# 5V_Power_Supply.net
KiCad netlist of a schematic drawn in Altium Designer
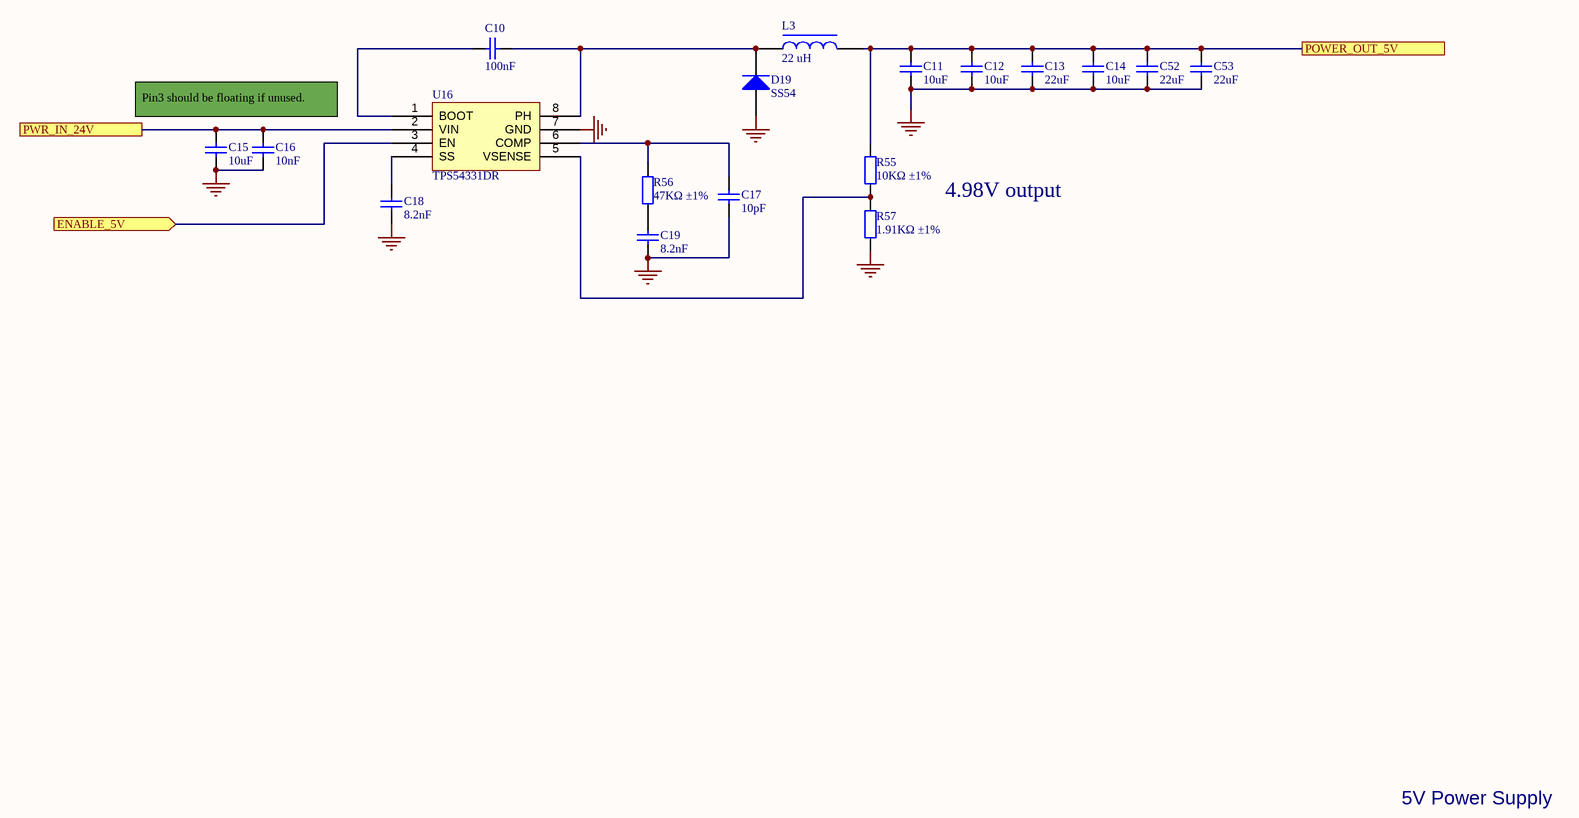
[diagram p0: 5V_Power_Supply.SchDoc]

(export (version "E")
  (design (tool "Eeschema 10.0.6"))
  (components
    (comp (ref "C10")
      (value "100nF")
      (footprint "0603_C")
      (description "50V 100nF X7R ±10% 0603 Multilayer Ceramic Capacitors MLCC - SMD/SMT ROHS")
      (fields
        (field (name "MANUFACTURER") "YAGEO")
        (field (name "MANUFACTURER PART NUMBER") "CC0603KRX7R9BB104")
      )
      (libsource (lib "Sienci_Labs") (part "0603 100nF (104) 10% 50V"))
    )
    (comp (ref "C11")
      (value "10uF")
      (footprint "1206_C")
      (description "50V 10uF X5R ±10% 1206 Multilayer Ceramic Capacitors MLCC - SMD/SMT ROHS")
      (fields
        (field (name "MANUFACTURER") "Samsung Electro-Mechanics")
        (field (name "MANUFACTURER PART NUMBER") "CL31A106KBHNNNE")
      )
      (libsource (lib "Sienci_Labs") (part "1206 10uF (106) 10% 50V"))
    )
    (comp (ref "C12")
      (value "10uF")
      (footprint "1206_C")
      (description "50V 10uF X5R ±10% 1206 Multilayer Ceramic Capacitors MLCC - SMD/SMT ROHS")
      (fields
        (field (name "MANUFACTURER") "Samsung Electro-Mechanics")
        (field (name "MANUFACTURER PART NUMBER") "CL31A106KBHNNNE")
      )
      (libsource (lib "Sienci_Labs") (part "1206 10uF (106) 10% 50V"))
    )
    (comp (ref "C13")
      (value "22uF")
      (footprint "0805_C")
      (description "25V 22uF X5R ±20% 0805 Multilayer Ceramic Capacitors MLCC - SMD/SMT ROHS")
      (fields (field (name "MANUFACTURER") "Samsung Electro-Mechanics") (field (name "TOLERANCE") "20%"))
      (libsource (lib "Sienci_Labs") (part "0805 22uF (226) 20% 25V"))
    )
    (comp (ref "C14")
      (value "10uF")
      (footprint "1206_C")
      (description "50V 10uF X5R ±10% 1206 Multilayer Ceramic Capacitors MLCC - SMD/SMT ROHS")
      (fields
        (field (name "MANUFACTURER") "Samsung Electro-Mechanics")
        (field (name "MANUFACTURER PART NUMBER") "CL31A106KBHNNNE")
      )
      (libsource (lib "Sienci_Labs") (part "1206 10uF (106) 10% 50V"))
    )
    (comp (ref "C15")
      (value "10uF")
      (footprint "1206_C")
      (description "50V 10uF X5R ±10% 1206 Multilayer Ceramic Capacitors MLCC - SMD/SMT ROHS")
      (fields
        (field (name "MANUFACTURER") "Samsung Electro-Mechanics")
        (field (name "MANUFACTURER PART NUMBER") "CL31A106KBHNNNE")
      )
      (libsource (lib "Sienci_Labs") (part "1206 10uF (106) 10% 50V"))
    )
    (comp (ref "C16")
      (value "10nF")
      (footprint "0603_C")
      (description "50V 10nF X7R ±10% 0603 Multilayer Ceramic Capacitors MLCC - SMD/SMT ROHS")
      (fields
        (field (name "MANUFACTURER") "Guangdong Fenghua Advanced Tech")
        (field (name "TOLERANCE") "10%")
      )
      (libsource (lib "Sienci_Labs") (part "0603 10nF (103) 10% 50V"))
    )
    (comp (ref "C17")
      (value "10pF")
      (footprint "0603_C")
      (description "Chip capacitors")
      (fields
        (field (name "MANUFACTURER") "Samsung Electro-Mechanics")
        (field (name "MANUFACTURER PART NUMBER") "CL10C100JB8NNNC")
      )
      (libsource (lib "Cap") (part "0603 10pF (100) 5% 50V"))
    )
    (comp (ref "C18")
      (value "8.2nF")
      (footprint "0603_C")
      (description "50V 8.2nF X7R ±10% 0603 Multilayer Ceramic Capacitors MLCC - SMD/SMT ROHS")
      (fields
        (field (name "MANUFACTURER") "YAGEO")
        (field (name "MANUFACTURER PART NUMBER") "CC0603KRX7R9BB822")
      )
      (libsource (lib "Sienci_Labs") (part "0603 8.2nF (822) 10% 50V"))
    )
    (comp (ref "C19")
      (value "8.2nF")
      (footprint "0603_C")
      (description "50V 8.2nF X7R ±10% 0603 Multilayer Ceramic Capacitors MLCC - SMD/SMT ROHS")
      (fields
        (field (name "MANUFACTURER") "YAGEO")
        (field (name "MANUFACTURER PART NUMBER") "CC0603KRX7R9BB822")
      )
      (libsource (lib "Sienci_Labs") (part "0603 8.2nF (822) 10% 50V"))
    )
    (comp (ref "C52")
      (value "22uF")
      (footprint "0805_C")
      (description "25V 22uF X5R ±20% 0805 Multilayer Ceramic Capacitors MLCC - SMD/SMT ROHS")
      (fields (field (name "MANUFACTURER") "Samsung Electro-Mechanics") (field (name "TOLERANCE") "20%"))
      (libsource (lib "Sienci_Labs") (part "0805 22uF (226) 20% 25V"))
    )
    (comp (ref "C53")
      (value "22uF")
      (footprint "0805_C")
      (description "25V 22uF X5R ±20% 0805 Multilayer Ceramic Capacitors MLCC - SMD/SMT ROHS")
      (fields (field (name "MANUFACTURER") "Samsung Electro-Mechanics") (field (name "TOLERANCE") "20%"))
      (libsource (lib "Sienci_Labs") (part "0805 22uF (226) 20% 25V"))
    )
    (comp (ref "D19")
      (value "SS54")
      (footprint "SMA(DO-214AC)_S1")
      (description "40V 5A 550mV@5A")
      (fields (field (name "MANUFACTURER") "MDD"))
      (libsource (lib "Diode") (part "SMA(DO-214AC) SS54"))
    )
    (comp (ref "L3")
      (value "22 uH")
      (footprint "INDPM7366X300N")
      (description "3A 22uH ±20% 130mΩ SMD,7.1x6.6x3mm Power Inductors ROHS")
      (fields
        (field (name "MANUFACTURER") "YJYCOIN")
        (field (name "MANUFACTURER PART NUMBER") "YSPI0630A-220M")
      )
      (libsource (lib "PrintNC_GRBLHAL_Breakout") (part "1206 10uH 10%"))
    )
    (comp (ref "R55")
      (value "10KΩ ±1%")
      (footprint "0603_R")
      (description "Chip resistor")
      (fields
        (field (name "MANUFACTURER") "Uniroyal Elec")
        (field (name "MANUFACTURER PART NUMBER") "0603WAF1002T5E")
      )
      (libsource (lib "RES") (part "0603 10K (1002) 1%"))
    )
    (comp (ref "R56")
      (value "47KΩ ±1%")
      (footprint "0603_R")
      (description "Chip resistor")
      (fields
        (field (name "MANUFACTURER") "Uniroyal Elec")
        (field (name "MANUFACTURER PART NUMBER") "0603WAF4702T5E")
      )
      (libsource (lib "RES") (part "0603 47K (4702) 1%"))
    )
    (comp (ref "R57")
      (value "1.91KΩ ±1%")
      (footprint "0603_R")
      (description "Chip resistor")
      (fields (field (name "MANUFACTURER") "TyoHM") (field (name "PARTNUMBER") "RMC06031.91K1%N"))
      (libsource (lib "RES") (part "0603 1.91K (2001) 1%"))
    )
    (comp (ref "U16")
      (value "TPS54331DR")
      (footprint "Miscellaneous Devices LC:SOIC-8_150mil")
      (description "Switching Voltage Regulators 3A 28V In Step Down SWIFT DC/DC Cnvrtr")
      (fields (field (name "MANUFACTURER") "Texas Instruments"))
      (libsource (lib "PrintNC_GRBLHAL_Breakout") (part "TPS54331DR_[C9865]"))
    )
  )
  (nets
    (net (code "1") (name "/ENABLE_5V") (class "Default")
      (node (ref "U16") (pin "3") (pinfunction "EN_3") (pintype "passive"))
    )
    (net (code "2") (name "/POWER_OUT_5V") (class "Default")
      (node (ref "C11") (pin "2") (pinfunction "2_2") (pintype "passive"))
      (node (ref "C12") (pin "2") (pinfunction "2_2") (pintype "passive"))
      (node (ref "C13") (pin "2") (pinfunction "2_2") (pintype "passive"))
      (node (ref "C14") (pin "2") (pinfunction "2_2") (pintype "passive"))
      (node (ref "C52") (pin "2") (pinfunction "2_2") (pintype "passive"))
      (node (ref "C53") (pin "2") (pinfunction "2_2") (pintype "passive"))
      (node (ref "L3") (pin "2") (pinfunction "2_2") (pintype "passive"))
      (node (ref "R55") (pin "2") (pinfunction "2_2") (pintype "passive"))
    )
    (net (code "3") (name "/PWR_IN_24V") (class "Default")
      (node (ref "C15") (pin "2") (pinfunction "2_2") (pintype "passive"))
      (node (ref "C16") (pin "2") (pinfunction "2_2") (pintype "passive"))
      (node (ref "U16") (pin "2") (pinfunction "VIN_2") (pintype "passive"))
    )
    (net (code "4") (name "GND") (class "Default")
      (node (ref "C11") (pin "1") (pinfunction "1_1") (pintype "passive"))
      (node (ref "C12") (pin "1") (pinfunction "1_1") (pintype "passive"))
      (node (ref "C13") (pin "1") (pinfunction "1_1") (pintype "passive"))
      (node (ref "C14") (pin "1") (pinfunction "1_1") (pintype "passive"))
      (node (ref "C15") (pin "1") (pinfunction "1_1") (pintype "passive"))
      (node (ref "C16") (pin "1") (pinfunction "1_1") (pintype "passive"))
      (node (ref "C17") (pin "1") (pinfunction "1_1") (pintype "passive"))
      (node (ref "C18") (pin "1") (pinfunction "1_1") (pintype "passive"))
      (node (ref "C19") (pin "1") (pinfunction "1_1") (pintype "passive"))
      (node (ref "C52") (pin "1") (pinfunction "1_1") (pintype "passive"))
      (node (ref "C53") (pin "1") (pinfunction "1_1") (pintype "passive"))
      (node (ref "D19") (pin "1") (pinfunction "A_1") (pintype "passive"))
      (node (ref "R57") (pin "1") (pinfunction "1_1") (pintype "passive"))
      (node (ref "U16") (pin "7") (pinfunction "GND_7") (pintype "passive"))
    )
    (net (code "5") (name "Net-(C19-Pad2)") (class "Default")
      (node (ref "C19") (pin "2") (pinfunction "2_2") (pintype "passive"))
      (node (ref "R56") (pin "1") (pinfunction "1_1") (pintype "passive"))
    )
    (net (code "6") (name "Net-(D19-K)") (class "Default")
      (node (ref "C10") (pin "2") (pinfunction "2_2") (pintype "passive"))
      (node (ref "D19") (pin "2") (pinfunction "K_2") (pintype "passive"))
      (node (ref "L3") (pin "1") (pinfunction "1_1") (pintype "passive"))
      (node (ref "U16") (pin "8") (pinfunction "PH_8") (pintype "passive"))
    )
    (net (code "7") (name "Net-(U16-BOOT)") (class "Default")
      (node (ref "C10") (pin "1") (pinfunction "1_1") (pintype "passive"))
      (node (ref "U16") (pin "1") (pinfunction "BOOT_1") (pintype "passive"))
    )
    (net (code "8") (name "Net-(U16-COMP)") (class "Default")
      (node (ref "C17") (pin "2") (pinfunction "2_2") (pintype "passive"))
      (node (ref "R56") (pin "2") (pinfunction "2_2") (pintype "passive"))
      (node (ref "U16") (pin "6") (pinfunction "COMP_6") (pintype "passive"))
    )
    (net (code "9") (name "Net-(U16-SS)") (class "Default")
      (node (ref "C18") (pin "2") (pinfunction "2_2") (pintype "passive"))
      (node (ref "U16") (pin "4") (pinfunction "SS_4") (pintype "passive"))
    )
    (net (code "10") (name "Net-(U16-VSENSE)") (class "Default")
      (node (ref "R55") (pin "1") (pinfunction "1_1") (pintype "passive"))
      (node (ref "R57") (pin "2") (pinfunction "2_2") (pintype "passive"))
      (node (ref "U16") (pin "5") (pinfunction "VSENSE_5") (pintype "passive"))
    )
  )
)
